# Sig_Acq.net
KiCad netlist of a schematic drawn in Altium Designer
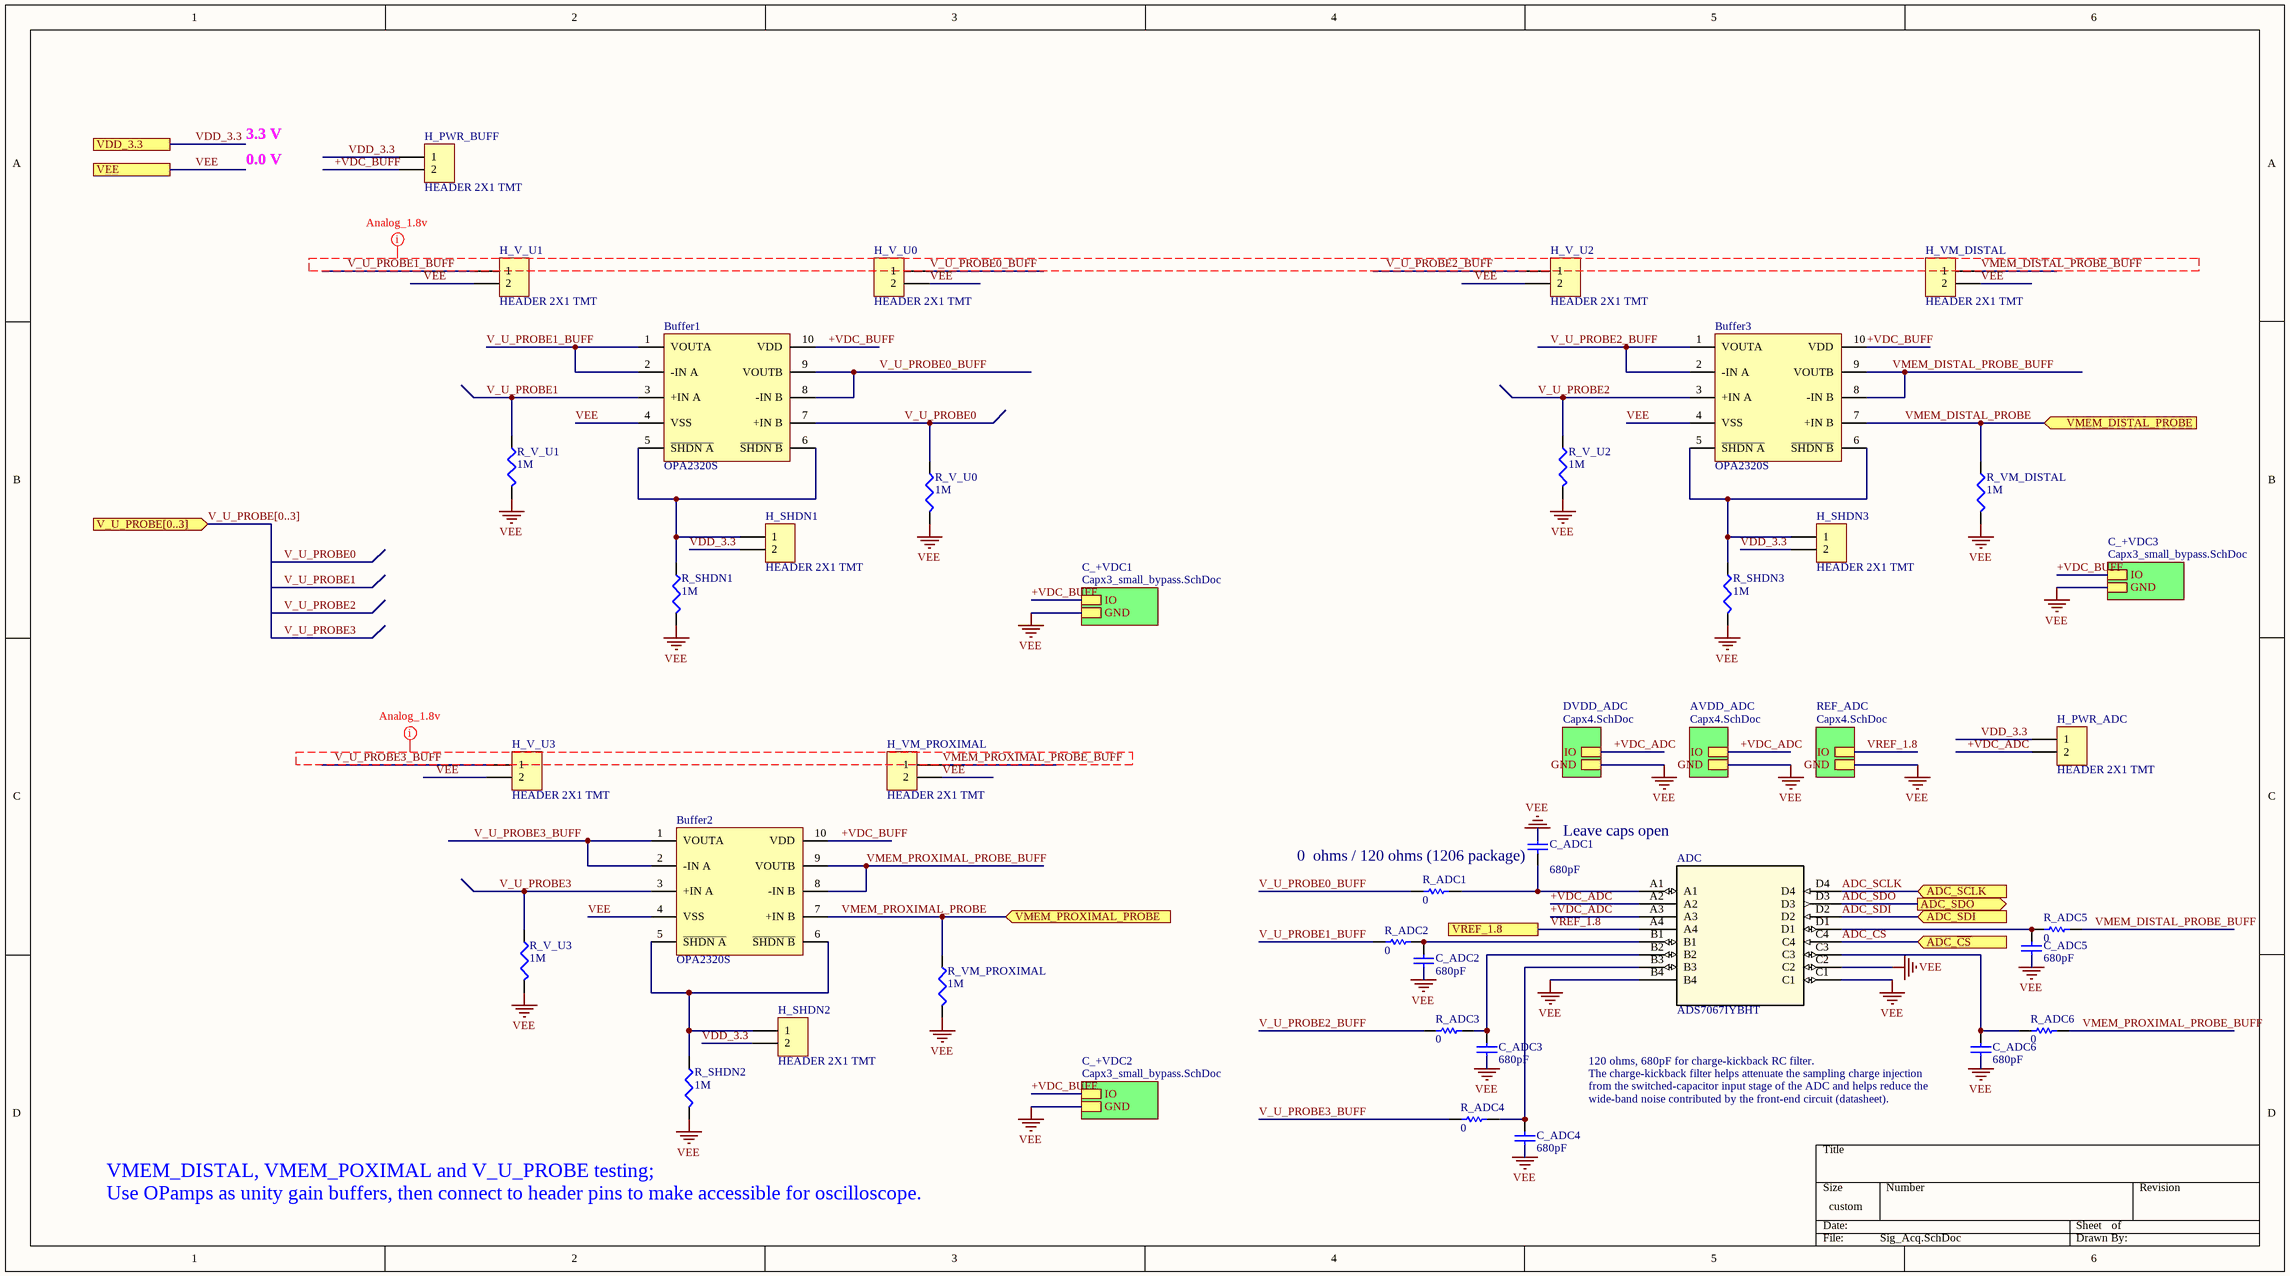
[diagram p0: Sig_Acq.SchDoc]

(export (version "E")
  (design (tool "Eeschema 10.0.6"))
  (components
    (comp (ref "ADC")
      (value "ADS7067IYBHT")
      (footprint "BGA16_YBH_TEX")
      (description "No Description Available")
      (fields (field (name "COPYRIGHT") "Copyright (C) 2022 Ultra Librarian. All rights reserved."))
      (libsource (lib "IFAT6") (part "ADS7067IYBHT"))
    )
    (comp (ref "Buffer1")
      (value "OPA2320S")
      (footprint "TI OPA2320SAIDGSR")
      (description "IC OPAMP RR CMOS 20MHZ 10VSSOP\r\nCMOS Amplifier Circuit Rail-to-Rail 10-VSSOP")
      (libsource (lib "IFAT6") (part "OPA2320S"))
    )
    (comp (ref "Buffer2")
      (value "OPA2320S")
      (footprint "TI OPA2320SAIDGSR")
      (description "IC OPAMP RR CMOS 20MHZ 10VSSOP\r\nCMOS Amplifier Circuit Rail-to-Rail 10-VSSOP")
      (libsource (lib "IFAT6") (part "OPA2320S"))
    )
    (comp (ref "Buffer3")
      (value "OPA2320S")
      (footprint "TI OPA2320SAIDGSR")
      (description "IC OPAMP RR CMOS 20MHZ 10VSSOP\r\nCMOS Amplifier Circuit Rail-to-Rail 10-VSSOP")
      (libsource (lib "IFAT6") (part "OPA2320S"))
    )
    (comp (ref "C_ADC1")
      (value "680pF")
      (footprint "THERM_NCP18XH103F03RB")
      (description "Capacitor")
      (fields (field (name "Comment") "Cap") (field (name "PUBLISHER") "Altium Limited"))
      (libsource (lib "Miscellaneous Devices") (part "Cap"))
    )
    (comp (ref "C_ADC2")
      (value "680pF")
      (footprint "THERM_NCP18XH103F03RB")
      (description "Capacitor")
      (fields (field (name "Comment") "Cap") (field (name "PUBLISHER") "Altium Limited"))
      (libsource (lib "Miscellaneous Devices") (part "Cap"))
    )
    (comp (ref "C_ADC3")
      (value "680pF")
      (footprint "THERM_NCP18XH103F03RB")
      (description "Capacitor")
      (fields (field (name "Comment") "Cap") (field (name "PUBLISHER") "Altium Limited"))
      (libsource (lib "Miscellaneous Devices") (part "Cap"))
    )
    (comp (ref "C_ADC4")
      (value "680pF")
      (footprint "THERM_NCP18XH103F03RB")
      (description "Capacitor")
      (fields (field (name "Comment") "Cap") (field (name "PUBLISHER") "Altium Limited"))
      (libsource (lib "Miscellaneous Devices") (part "Cap"))
    )
    (comp (ref "C_ADC5")
      (value "680pF")
      (footprint "THERM_NCP18XH103F03RB")
      (description "Capacitor")
      (fields (field (name "Comment") "Cap") (field (name "PUBLISHER") "Altium Limited"))
      (libsource (lib "Miscellaneous Devices") (part "Cap"))
    )
    (comp (ref "C_ADC6")
      (value "680pF")
      (footprint "THERM_NCP18XH103F03RB")
      (description "Capacitor")
      (fields (field (name "Comment") "Cap") (field (name "PUBLISHER") "Altium Limited"))
      (libsource (lib "Miscellaneous Devices") (part "Cap"))
    )
    (comp (ref "H_PWR_ADC")
      (value "HEADER 2X1 TMT")
      (footprint "Samtec TSW-102-07-G-S")
      (description "CONN HEADER VERT 2POS 2.54MM\r\nConnector Header Through Hole 2 position 0.100\" (2.54mm)")
      (libsource (lib "IFAT6") (part "HEADER 2X1 TMT"))
    )
    (comp (ref "H_PWR_BUFF")
      (value "HEADER 2X1 TMT")
      (footprint "Samtec TSW-102-07-G-S")
      (description "CONN HEADER VERT 2POS 2.54MM\r\nConnector Header Through Hole 2 position 0.100\" (2.54mm)")
      (libsource (lib "IFAT6") (part "HEADER 2X1 TMT"))
    )
    (comp (ref "H_SHDN1")
      (value "HEADER 2X1 TMT")
      (footprint "Samtec TSW-102-07-G-S")
      (description "CONN HEADER VERT 2POS 2.54MM\r\nConnector Header Through Hole 2 position 0.100\" (2.54mm)")
      (libsource (lib "MRI_ADC") (part "HEADER 2X1 TMT"))
    )
    (comp (ref "H_SHDN2")
      (value "HEADER 2X1 TMT")
      (footprint "Samtec TSW-102-07-G-S")
      (description "CONN HEADER VERT 2POS 2.54MM\r\nConnector Header Through Hole 2 position 0.100\" (2.54mm)")
      (libsource (lib "MRI_ADC") (part "HEADER 2X1 TMT"))
    )
    (comp (ref "H_SHDN3")
      (value "HEADER 2X1 TMT")
      (footprint "Samtec TSW-102-07-G-S")
      (description "CONN HEADER VERT 2POS 2.54MM\r\nConnector Header Through Hole 2 position 0.100\" (2.54mm)")
      (libsource (lib "MRI_ADC") (part "HEADER 2X1 TMT"))
    )
    (comp (ref "H_VM_DISTAL")
      (value "HEADER 2X1 TMT")
      (footprint "Samtec TSW-102-07-G-S")
      (description "CONN HEADER VERT 2POS 2.54MM\r\nConnector Header Through Hole 2 position 0.100\" (2.54mm)")
      (libsource (lib "") (part "HEADER 2X1 TMT_1"))
    )
    (comp (ref "H_VM_PROXIMAL")
      (value "HEADER 2X1 TMT")
      (footprint "Samtec TSW-102-07-G-S")
      (description "CONN HEADER VERT 2POS 2.54MM\r\nConnector Header Through Hole 2 position 0.100\" (2.54mm)")
      (libsource (lib "") (part "HEADER 2X1 TMT_1"))
    )
    (comp (ref "H_V_U0")
      (value "HEADER 2X1 TMT")
      (footprint "Samtec TSW-102-07-G-S")
      (description "CONN HEADER VERT 2POS 2.54MM\r\nConnector Header Through Hole 2 position 0.100\" (2.54mm)")
      (libsource (lib "") (part "HEADER 2X1 TMT_1"))
    )
    (comp (ref "H_V_U1")
      (value "HEADER 2X1 TMT")
      (footprint "Samtec TSW-102-07-G-S")
      (description "CONN HEADER VERT 2POS 2.54MM\r\nConnector Header Through Hole 2 position 0.100\" (2.54mm)")
      (libsource (lib "MRI_ADC") (part "HEADER 2X1 TMT"))
    )
    (comp (ref "H_V_U2")
      (value "HEADER 2X1 TMT")
      (footprint "Samtec TSW-102-07-G-S")
      (description "CONN HEADER VERT 2POS 2.54MM\r\nConnector Header Through Hole 2 position 0.100\" (2.54mm)")
      (libsource (lib "MRI_ADC") (part "HEADER 2X1 TMT"))
    )
    (comp (ref "H_V_U3")
      (value "HEADER 2X1 TMT")
      (footprint "Samtec TSW-102-07-G-S")
      (description "CONN HEADER VERT 2POS 2.54MM\r\nConnector Header Through Hole 2 position 0.100\" (2.54mm)")
      (libsource (lib "MRI_ADC") (part "HEADER 2X1 TMT"))
    )
    (comp (ref "R_ADC1")
      (value "0")
      (footprint "RESC3216X70X50NL05T20")
      (fields (field (name "MANUFACTURER") "Panasonic") (field (name "PART NUMBER") "ERJ-8GEY0R00V"))
      (libsource (lib "Altium Content Vault") (part "RES"))
    )
    (comp (ref "R_ADC2")
      (value "0")
      (footprint "RESC3216X70X50NL05T20")
      (fields (field (name "MANUFACTURER") "Panasonic") (field (name "PART NUMBER") "ERJ-8GEY0R00V"))
      (libsource (lib "Altium Content Vault") (part "RES"))
    )
    (comp (ref "R_ADC3")
      (value "0")
      (footprint "RESC3216X70X50NL05T20")
      (fields (field (name "MANUFACTURER") "Panasonic") (field (name "PART NUMBER") "ERJ-8GEY0R00V"))
      (libsource (lib "Altium Content Vault") (part "RES"))
    )
    (comp (ref "R_ADC4")
      (value "0")
      (footprint "RESC3216X70X50NL05T20")
      (fields (field (name "MANUFACTURER") "Panasonic") (field (name "PART NUMBER") "ERJ-8GEY0R00V"))
      (libsource (lib "Altium Content Vault") (part "RES"))
    )
    (comp (ref "R_ADC5")
      (value "0")
      (footprint "RESC3216X70X50NL05T20")
      (fields (field (name "MANUFACTURER") "Panasonic") (field (name "PART NUMBER") "ERJ-8GEY0R00V"))
      (libsource (lib "Altium Content Vault") (part "RES"))
    )
    (comp (ref "R_ADC6")
      (value "0")
      (footprint "RESC3216X70X50NL05T20")
      (fields (field (name "MANUFACTURER") "Panasonic") (field (name "PART NUMBER") "ERJ-8GEY0R00V"))
      (libsource (lib "Altium Content Vault") (part "RES"))
    )
    (comp (ref "R_SHDN1")
      (value "1M")
      (footprint "Panasonic ERA-6A Series Resistor")
      (fields (field (name "Comment") "Res 1M 0.1% 0805"))
      (libsource (lib "MRI_ADC") (part "Res 1M 0.1% 0805"))
    )
    (comp (ref "R_SHDN2")
      (value "1M")
      (footprint "Panasonic ERA-6A Series Resistor")
      (fields (field (name "Comment") "Res 1M 0.1% 0805"))
      (libsource (lib "MRI_ADC") (part "Res 1M 0.1% 0805"))
    )
    (comp (ref "R_SHDN3")
      (value "1M")
      (footprint "Panasonic ERA-6A Series Resistor")
      (fields (field (name "Comment") "Res 1M 0.1% 0805"))
      (libsource (lib "MRI_ADC") (part "Res 1M 0.1% 0805"))
    )
    (comp (ref "R_VM_DISTAL")
      (value "1M")
      (footprint "Panasonic ERA-6A Series Resistor")
      (fields (field (name "Comment") "Res 1M 0.1% 0805"))
      (libsource (lib "MRI_ADC") (part "Res 1M 0.1% 0805"))
    )
    (comp (ref "R_VM_PROXIMAL")
      (value "1M")
      (footprint "Panasonic ERA-6A Series Resistor")
      (fields (field (name "Comment") "Res 1M 0.1% 0805"))
      (libsource (lib "MRI_ADC") (part "Res 1M 0.1% 0805"))
    )
    (comp (ref "R_V_U0")
      (value "1M")
      (footprint "Panasonic ERA-6A Series Resistor")
      (fields (field (name "Comment") "Res 1M 0.1% 0805"))
      (libsource (lib "MRI_ADC") (part "Res 1M 0.1% 0805"))
    )
    (comp (ref "R_V_U1")
      (value "1M")
      (footprint "Panasonic ERA-6A Series Resistor")
      (fields (field (name "Comment") "Res 1M 0.1% 0805"))
      (libsource (lib "MRI_ADC") (part "Res 1M 0.1% 0805"))
    )
    (comp (ref "R_V_U2")
      (value "1M")
      (footprint "Panasonic ERA-6A Series Resistor")
      (fields (field (name "Comment") "Res 1M 0.1% 0805"))
      (libsource (lib "MRI_ADC") (part "Res 1M 0.1% 0805"))
    )
    (comp (ref "R_V_U3")
      (value "1M")
      (footprint "Panasonic ERA-6A Series Resistor")
      (fields (field (name "Comment") "Res 1M 0.1% 0805"))
      (libsource (lib "MRI_ADC") (part "Res 1M 0.1% 0805"))
    )
  )
  (nets
    (net (code "1") (name "/+VDC_ADC") (class "Default")
      (node (ref "ADC") (pin "A2") (pinfunction "A2_A2") (pintype "power_in"))
      (node (ref "ADC") (pin "A3") (pinfunction "A3_A3") (pintype "power_in"))
      (node (ref "H_PWR_ADC") (pin "2") (pinfunction "2_2") (pintype "passive"))
    )
    (net (code "2") (name "/+VDC_BUFF") (class "Default")
      (node (ref "Buffer1") (pin "10") (pinfunction "VDD_10") (pintype "passive"))
      (node (ref "Buffer2") (pin "10") (pinfunction "VDD_10") (pintype "passive"))
      (node (ref "Buffer3") (pin "10") (pinfunction "VDD_10") (pintype "passive"))
      (node (ref "H_PWR_BUFF") (pin "2") (pinfunction "2_2") (pintype "passive"))
    )
    (net (code "3") (name "/ADC_SCLK") (class "Default")
      (node (ref "ADC") (pin "D4") (pinfunction "D4_D4") (pintype "input"))
    )
    (net (code "4") (name "/ADC_SDI") (class "Default")
      (node (ref "ADC") (pin "D2") (pinfunction "D2_D2") (pintype "input"))
    )
    (net (code "5") (name "/ADC_SDO") (class "Default")
      (node (ref "ADC") (pin "D3") (pinfunction "D3_D3") (pintype "output"))
    )
    (net (code "6") (name "/ADC_~{CS}") (class "Default")
      (node (ref "ADC") (pin "C4") (pinfunction "C4_C4") (pintype "input"))
    )
    (net (code "7") (name "/VDD_3.3") (class "Default")
      (node (ref "H_PWR_ADC") (pin "1") (pinfunction "1_1") (pintype "passive"))
      (node (ref "H_PWR_BUFF") (pin "1") (pinfunction "1_1") (pintype "passive"))
      (node (ref "H_SHDN1") (pin "2") (pinfunction "2_2") (pintype "passive"))
      (node (ref "H_SHDN2") (pin "2") (pinfunction "2_2") (pintype "passive"))
      (node (ref "H_SHDN3") (pin "2") (pinfunction "2_2") (pintype "passive"))
    )
    (net (code "8") (name "/VMEM_DISTAL_PROBE") (class "Default")
      (node (ref "Buffer3") (pin "7") (pinfunction "+IN_B_7") (pintype "passive"))
      (node (ref "R_VM_DISTAL") (pin "1") (pinfunction "1_1") (pintype "passive"))
    )
    (net (code "9") (name "/VMEM_DISTAL_PROBE_BUFF") (class "Default")
      (node (ref "Buffer3") (pin "8") (pinfunction "-IN_B_8") (pintype "passive"))
      (node (ref "Buffer3") (pin "9") (pinfunction "VOUTB_9") (pintype "passive"))
      (node (ref "H_VM_DISTAL") (pin "1") (pinfunction "1_1") (pintype "passive"))
      (node (ref "R_ADC5") (pin "2") (pinfunction "2_2") (pintype "passive"))
    )
    (net (code "10") (name "/VMEM_PROXIMAL_PROBE") (class "Default")
      (node (ref "Buffer2") (pin "7") (pinfunction "+IN_B_7") (pintype "passive"))
      (node (ref "R_VM_PROXIMAL") (pin "1") (pinfunction "1_1") (pintype "passive"))
    )
    (net (code "11") (name "/VMEM_PROXIMAL_PROBE_BUFF") (class "Default")
      (node (ref "Buffer2") (pin "8") (pinfunction "-IN_B_8") (pintype "passive"))
      (node (ref "Buffer2") (pin "9") (pinfunction "VOUTB_9") (pintype "passive"))
      (node (ref "H_VM_PROXIMAL") (pin "1") (pinfunction "1_1") (pintype "passive"))
      (node (ref "R_ADC6") (pin "2") (pinfunction "2_2") (pintype "passive"))
    )
    (net (code "12") (name "/VREF_1.8") (class "Default")
      (node (ref "ADC") (pin "A4") (pinfunction "A4_A4") (pintype "power_in"))
    )
    (net (code "13") (name "/V_U_PROBE0") (class "Default")
      (node (ref "Buffer1") (pin "7") (pinfunction "+IN_B_7") (pintype "passive"))
      (node (ref "R_V_U0") (pin "1") (pinfunction "1_1") (pintype "passive"))
    )
    (net (code "14") (name "/V_U_PROBE0_BUFF") (class "Default")
      (node (ref "Buffer1") (pin "8") (pinfunction "-IN_B_8") (pintype "passive"))
      (node (ref "Buffer1") (pin "9") (pinfunction "VOUTB_9") (pintype "passive"))
      (node (ref "H_V_U0") (pin "1") (pinfunction "1_1") (pintype "passive"))
      (node (ref "R_ADC1") (pin "1") (pinfunction "1_1") (pintype "passive"))
    )
    (net (code "15") (name "/V_U_PROBE1") (class "Default")
      (node (ref "Buffer1") (pin "3") (pinfunction "+IN_A_3") (pintype "passive"))
      (node (ref "R_V_U1") (pin "1") (pinfunction "1_1") (pintype "passive"))
    )
    (net (code "16") (name "/V_U_PROBE1_BUFF") (class "Default")
      (node (ref "Buffer1") (pin "1") (pinfunction "VOUTA_1") (pintype "passive"))
      (node (ref "Buffer1") (pin "2") (pinfunction "-IN_A_2") (pintype "passive"))
      (node (ref "H_V_U1") (pin "1") (pinfunction "1_1") (pintype "passive"))
      (node (ref "R_ADC2") (pin "1") (pinfunction "1_1") (pintype "passive"))
    )
    (net (code "17") (name "/V_U_PROBE2") (class "Default")
      (node (ref "Buffer3") (pin "3") (pinfunction "+IN_A_3") (pintype "passive"))
      (node (ref "R_V_U2") (pin "1") (pinfunction "1_1") (pintype "passive"))
    )
    (net (code "18") (name "/V_U_PROBE2_BUFF") (class "Default")
      (node (ref "Buffer3") (pin "1") (pinfunction "VOUTA_1") (pintype "passive"))
      (node (ref "Buffer3") (pin "2") (pinfunction "-IN_A_2") (pintype "passive"))
      (node (ref "H_V_U2") (pin "1") (pinfunction "1_1") (pintype "passive"))
      (node (ref "R_ADC3") (pin "1") (pinfunction "1_1") (pintype "passive"))
    )
    (net (code "19") (name "/V_U_PROBE3") (class "Default")
      (node (ref "Buffer2") (pin "3") (pinfunction "+IN_A_3") (pintype "passive"))
      (node (ref "R_V_U3") (pin "1") (pinfunction "1_1") (pintype "passive"))
    )
    (net (code "20") (name "/V_U_PROBE3_BUFF") (class "Default")
      (node (ref "Buffer2") (pin "1") (pinfunction "VOUTA_1") (pintype "passive"))
      (node (ref "Buffer2") (pin "2") (pinfunction "-IN_A_2") (pintype "passive"))
      (node (ref "H_V_U3") (pin "1") (pinfunction "1_1") (pintype "passive"))
      (node (ref "R_ADC4") (pin "1") (pinfunction "1_1") (pintype "passive"))
    )
    (net (code "22") (name "Net-(ADC-PadA1)") (class "Default")
      (node (ref "ADC") (pin "A1") (pinfunction "A1_A1") (pintype "bidirectional"))
      (node (ref "C_ADC1") (pin "1") (pinfunction "1_1") (pintype "passive"))
      (node (ref "R_ADC1") (pin "2") (pinfunction "2_2") (pintype "passive"))
    )
    (net (code "23") (name "Net-(ADC-PadB1)") (class "Default")
      (node (ref "ADC") (pin "B1") (pinfunction "B1_B1") (pintype "bidirectional"))
      (node (ref "C_ADC2") (pin "1") (pinfunction "1_1") (pintype "passive"))
      (node (ref "R_ADC2") (pin "2") (pinfunction "2_2") (pintype "passive"))
    )
    (net (code "24") (name "Net-(ADC-PadB2)") (class "Default")
      (node (ref "ADC") (pin "B2") (pinfunction "B2_B2") (pintype "bidirectional"))
      (node (ref "C_ADC3") (pin "1") (pinfunction "1_1") (pintype "passive"))
      (node (ref "R_ADC3") (pin "2") (pinfunction "2_2") (pintype "passive"))
    )
    (net (code "25") (name "Net-(ADC-PadB3)") (class "Default")
      (node (ref "ADC") (pin "B3") (pinfunction "B3_B3") (pintype "bidirectional"))
      (node (ref "C_ADC4") (pin "1") (pinfunction "1_1") (pintype "passive"))
      (node (ref "R_ADC4") (pin "2") (pinfunction "2_2") (pintype "passive"))
    )
    (net (code "26") (name "Net-(ADC-PadC3)") (class "Default")
      (node (ref "ADC") (pin "C3") (pinfunction "C3_C3") (pintype "bidirectional"))
      (node (ref "C_ADC6") (pin "1") (pinfunction "1_1") (pintype "passive"))
      (node (ref "R_ADC6") (pin "1") (pinfunction "1_1") (pintype "passive"))
    )
    (net (code "27") (name "Net-(ADC-PadD1)") (class "Default")
      (node (ref "ADC") (pin "D1") (pinfunction "D1_D1") (pintype "bidirectional"))
      (node (ref "C_ADC5") (pin "1") (pinfunction "1_1") (pintype "passive"))
      (node (ref "R_ADC5") (pin "1") (pinfunction "1_1") (pintype "passive"))
    )
    (net (code "28") (name "Net-(Buffer1-~{SHDN_A})") (class "Default")
      (node (ref "Buffer1") (pin "5") (pinfunction "~{SHDN_A}_5") (pintype "passive"))
      (node (ref "Buffer1") (pin "6") (pinfunction "~{SHDN_B}_6") (pintype "passive"))
      (node (ref "H_SHDN1") (pin "1") (pinfunction "1_1") (pintype "passive"))
      (node (ref "R_SHDN1") (pin "1") (pinfunction "1_1") (pintype "passive"))
    )
    (net (code "29") (name "Net-(Buffer2-~{SHDN_A})") (class "Default")
      (node (ref "Buffer2") (pin "5") (pinfunction "~{SHDN_A}_5") (pintype "passive"))
      (node (ref "Buffer2") (pin "6") (pinfunction "~{SHDN_B}_6") (pintype "passive"))
      (node (ref "H_SHDN2") (pin "1") (pinfunction "1_1") (pintype "passive"))
      (node (ref "R_SHDN2") (pin "1") (pinfunction "1_1") (pintype "passive"))
    )
    (net (code "30") (name "Net-(Buffer3-~{SHDN_A})") (class "Default")
      (node (ref "Buffer3") (pin "5") (pinfunction "~{SHDN_A}_5") (pintype "passive"))
      (node (ref "Buffer3") (pin "6") (pinfunction "~{SHDN_B}_6") (pintype "passive"))
      (node (ref "H_SHDN3") (pin "1") (pinfunction "1_1") (pintype "passive"))
      (node (ref "R_SHDN3") (pin "1") (pinfunction "1_1") (pintype "passive"))
    )
    (net (code "31") (name "VEE") (class "Default")
      (node (ref "ADC") (pin "B4") (pinfunction "B4_B4") (pintype "passive"))
      (node (ref "ADC") (pin "C1") (pinfunction "C1_C1") (pintype "bidirectional"))
      (node (ref "ADC") (pin "C2") (pinfunction "C2_C2") (pintype "bidirectional"))
      (node (ref "Buffer1") (pin "4") (pinfunction "VSS_4") (pintype "passive"))
      (node (ref "Buffer2") (pin "4") (pinfunction "VSS_4") (pintype "passive"))
      (node (ref "Buffer3") (pin "4") (pinfunction "VSS_4") (pintype "passive"))
      (node (ref "C_ADC1") (pin "2") (pinfunction "2_2") (pintype "passive"))
      (node (ref "C_ADC2") (pin "2") (pinfunction "2_2") (pintype "passive"))
      (node (ref "C_ADC3") (pin "2") (pinfunction "2_2") (pintype "passive"))
      (node (ref "C_ADC4") (pin "2") (pinfunction "2_2") (pintype "passive"))
      (node (ref "C_ADC5") (pin "2") (pinfunction "2_2") (pintype "passive"))
      (node (ref "C_ADC6") (pin "2") (pinfunction "2_2") (pintype "passive"))
      (node (ref "H_VM_DISTAL") (pin "2") (pinfunction "2_2") (pintype "passive"))
      (node (ref "H_VM_PROXIMAL") (pin "2") (pinfunction "2_2") (pintype "passive"))
      (node (ref "H_V_U0") (pin "2") (pinfunction "2_2") (pintype "passive"))
      (node (ref "H_V_U1") (pin "2") (pinfunction "2_2") (pintype "passive"))
      (node (ref "H_V_U2") (pin "2") (pinfunction "2_2") (pintype "passive"))
      (node (ref "H_V_U3") (pin "2") (pinfunction "2_2") (pintype "passive"))
      (node (ref "R_SHDN1") (pin "2") (pinfunction "2_2") (pintype "passive"))
      (node (ref "R_SHDN2") (pin "2") (pinfunction "2_2") (pintype "passive"))
      (node (ref "R_SHDN3") (pin "2") (pinfunction "2_2") (pintype "passive"))
      (node (ref "R_VM_DISTAL") (pin "2") (pinfunction "2_2") (pintype "passive"))
      (node (ref "R_VM_PROXIMAL") (pin "2") (pinfunction "2_2") (pintype "passive"))
      (node (ref "R_V_U0") (pin "2") (pinfunction "2_2") (pintype "passive"))
      (node (ref "R_V_U1") (pin "2") (pinfunction "2_2") (pintype "passive"))
      (node (ref "R_V_U2") (pin "2") (pinfunction "2_2") (pintype "passive"))
      (node (ref "R_V_U3") (pin "2") (pinfunction "2_2") (pintype "passive"))
    )
  )
)
